# FlexSensor_and_Servo.net
KiCad netlist of a schematic drawn in EAGLE
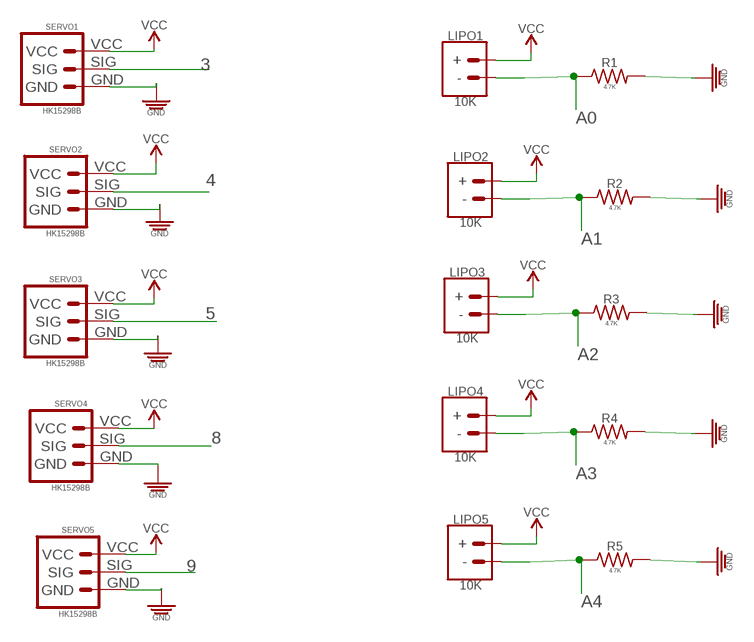
[diagram p0: schematic, sheet 1]

(export (version "E")
  (design (tool "Eeschema 10.0.6"))
  (components
    (comp (ref "LIPO1")
      (value "10K")
      (footprint "eagle-import:_MOLEX-89400_VERT_PITCH-2MM")
      (fields (field (name "MFR") "Spectra Symbol") (field (name "MPN") "FS-L-0095-103-ST"))
      (libsource (lib "eagle-import") (part "FLEX_SENSOR_89400_VERT-MALE_PITCH-2MM"))
    )
    (comp (ref "LIPO2")
      (value "10K")
      (footprint "eagle-import:_MOLEX-89400_VERT_PITCH-2MM")
      (fields (field (name "MFR") "Spectra Symbol") (field (name "MPN") "FS-L-0095-103-ST"))
      (libsource (lib "eagle-import") (part "FLEX_SENSOR_89400_VERT-MALE_PITCH-2MM"))
    )
    (comp (ref "LIPO3")
      (value "10K")
      (footprint "eagle-import:_MOLEX-89400_VERT_PITCH-2MM")
      (fields (field (name "MFR") "Spectra Symbol") (field (name "MPN") "FS-L-0095-103-ST"))
      (libsource (lib "eagle-import") (part "FLEX_SENSOR_89400_VERT-MALE_PITCH-2MM"))
    )
    (comp (ref "LIPO4")
      (value "10K")
      (footprint "eagle-import:_MOLEX-89400_VERT_PITCH-2MM")
      (fields (field (name "MFR") "Spectra Symbol") (field (name "MPN") "FS-L-0095-103-ST"))
      (libsource (lib "eagle-import") (part "FLEX_SENSOR_89400_VERT-MALE_PITCH-2MM"))
    )
    (comp (ref "LIPO5")
      (value "10K")
      (footprint "eagle-import:_MOLEX-89400_VERT_PITCH-2MM")
      (fields (field (name "MFR") "Spectra Symbol") (field (name "MPN") "FS-L-0095-103-ST"))
      (libsource (lib "eagle-import") (part "FLEX_SENSOR_89400_VERT-MALE_PITCH-2MM"))
    )
    (comp (ref "R1")
      (value "4.7K")
      (footprint "eagle-import:RESISTOR_SMD-805")
      (fields
        (field (name "MFR") "Yageo")
        (field (name "MPN") "RC0805JR-074K7L")
        (field (name "CREATOR") "MrSwirlyEyes")
      )
      (libsource (lib "eagle-import") (part "4.7KΩ_SMD-0805_1/8W-5%"))
    )
    (comp (ref "R2")
      (value "4.7K")
      (footprint "eagle-import:RESISTOR_SMD-805")
      (fields
        (field (name "MFR") "Yageo")
        (field (name "MPN") "RC0805JR-074K7L")
        (field (name "CREATOR") "MrSwirlyEyes")
      )
      (libsource (lib "eagle-import") (part "4.7KΩ_SMD-0805_1/8W-5%"))
    )
    (comp (ref "R3")
      (value "4.7K")
      (footprint "eagle-import:RESISTOR_SMD-805")
      (fields
        (field (name "MFR") "Yageo")
        (field (name "MPN") "RC0805JR-074K7L")
        (field (name "CREATOR") "MrSwirlyEyes")
      )
      (libsource (lib "eagle-import") (part "4.7KΩ_SMD-0805_1/8W-5%"))
    )
    (comp (ref "R4")
      (value "4.7K")
      (footprint "eagle-import:RESISTOR_SMD-805")
      (fields
        (field (name "MFR") "Yageo")
        (field (name "MPN") "RC0805JR-074K7L")
        (field (name "CREATOR") "MrSwirlyEyes")
      )
      (libsource (lib "eagle-import") (part "4.7KΩ_SMD-0805_1/8W-5%"))
    )
    (comp (ref "R5")
      (value "4.7K")
      (footprint "eagle-import:RESISTOR_SMD-805")
      (fields
        (field (name "MFR") "Yageo")
        (field (name "MPN") "RC0805JR-074K7L")
        (field (name "CREATOR") "MrSwirlyEyes")
      )
      (libsource (lib "eagle-import") (part "4.7KΩ_SMD-0805_1/8W-5%"))
    )
    (comp (ref "SERVO1")
      (value "HK15298B")
      (footprint "eagle-import:1X03-VERT-MALE")
      (fields (field (name "MFR") "HobbyKing"))
      (libsource (lib "eagle-import") (part "SERVO_SERVO-PN"))
    )
    (comp (ref "SERVO2")
      (value "HK15298B")
      (footprint "eagle-import:1X03-VERT-MALE")
      (fields (field (name "MFR") "HobbyKing"))
      (libsource (lib "eagle-import") (part "SERVO_SERVO-PN"))
    )
    (comp (ref "SERVO3")
      (value "HK15298B")
      (footprint "eagle-import:1X03-VERT-MALE")
      (fields (field (name "MFR") "HobbyKing"))
      (libsource (lib "eagle-import") (part "SERVO_SERVO-PN"))
    )
    (comp (ref "SERVO4")
      (value "HK15298B")
      (footprint "eagle-import:1X03-VERT-MALE")
      (fields (field (name "MFR") "HobbyKing"))
      (libsource (lib "eagle-import") (part "SERVO_SERVO-PN"))
    )
    (comp (ref "SERVO5")
      (value "HK15298B")
      (footprint "eagle-import:1X03-VERT-MALE")
      (fields (field (name "MFR") "HobbyKing"))
      (libsource (lib "eagle-import") (part "SERVO_SERVO-PN"))
    )
  )
  (nets
    (net (code "1") (name "/3") (class "Default")
      (node (ref "SERVO1") (pin "SIG") (pinfunction "SIG_SIG") (pintype "passive"))
    )
    (net (code "2") (name "/4") (class "Default")
      (node (ref "SERVO2") (pin "SIG") (pinfunction "SIG_SIG") (pintype "passive"))
    )
    (net (code "3") (name "/5") (class "Default")
      (node (ref "SERVO3") (pin "SIG") (pinfunction "SIG_SIG") (pintype "passive"))
    )
    (net (code "4") (name "/8") (class "Default")
      (node (ref "SERVO4") (pin "SIG") (pinfunction "SIG_SIG") (pintype "passive"))
    )
    (net (code "5") (name "/9") (class "Default")
      (node (ref "SERVO5") (pin "SIG") (pinfunction "SIG_SIG") (pintype "passive"))
    )
    (net (code "6") (name "/A0") (class "Default")
      (node (ref "LIPO1") (pin "2") (pinfunction "-_2") (pintype "passive"))
      (node (ref "R1") (pin "1") (pinfunction "1_1") (pintype "passive"))
    )
    (net (code "7") (name "/A1") (class "Default")
      (node (ref "LIPO2") (pin "2") (pinfunction "-_2") (pintype "passive"))
      (node (ref "R2") (pin "1") (pinfunction "1_1") (pintype "passive"))
    )
    (net (code "8") (name "/A2") (class "Default")
      (node (ref "LIPO3") (pin "2") (pinfunction "-_2") (pintype "passive"))
      (node (ref "R3") (pin "1") (pinfunction "1_1") (pintype "passive"))
    )
    (net (code "9") (name "/A3") (class "Default")
      (node (ref "LIPO4") (pin "2") (pinfunction "-_2") (pintype "passive"))
      (node (ref "R4") (pin "1") (pinfunction "1_1") (pintype "passive"))
    )
    (net (code "10") (name "/A4") (class "Default")
      (node (ref "LIPO5") (pin "2") (pinfunction "-_2") (pintype "passive"))
      (node (ref "R5") (pin "1") (pinfunction "1_1") (pintype "passive"))
    )
    (net (code "11") (name "GND") (class "Default")
      (node (ref "R1") (pin "2") (pinfunction "2_2") (pintype "passive"))
      (node (ref "R2") (pin "2") (pinfunction "2_2") (pintype "passive"))
      (node (ref "R3") (pin "2") (pinfunction "2_2") (pintype "passive"))
      (node (ref "R4") (pin "2") (pinfunction "2_2") (pintype "passive"))
      (node (ref "R5") (pin "2") (pinfunction "2_2") (pintype "passive"))
      (node (ref "SERVO1") (pin "GND") (pinfunction "GND_GND") (pintype "passive"))
      (node (ref "SERVO2") (pin "GND") (pinfunction "GND_GND") (pintype "passive"))
      (node (ref "SERVO3") (pin "GND") (pinfunction "GND_GND") (pintype "passive"))
      (node (ref "SERVO4") (pin "GND") (pinfunction "GND_GND") (pintype "passive"))
      (node (ref "SERVO5") (pin "GND") (pinfunction "GND_GND") (pintype "passive"))
    )
    (net (code "12") (name "VCC") (class "Default")
      (node (ref "LIPO1") (pin "1") (pinfunction "+_1") (pintype "passive"))
      (node (ref "LIPO2") (pin "1") (pinfunction "+_1") (pintype "passive"))
      (node (ref "LIPO3") (pin "1") (pinfunction "+_1") (pintype "passive"))
      (node (ref "LIPO4") (pin "1") (pinfunction "+_1") (pintype "passive"))
      (node (ref "LIPO5") (pin "1") (pinfunction "+_1") (pintype "passive"))
      (node (ref "SERVO1") (pin "VCC") (pinfunction "VCC_VCC") (pintype "passive"))
      (node (ref "SERVO2") (pin "VCC") (pinfunction "VCC_VCC") (pintype "passive"))
      (node (ref "SERVO3") (pin "VCC") (pinfunction "VCC_VCC") (pintype "passive"))
      (node (ref "SERVO4") (pin "VCC") (pinfunction "VCC_VCC") (pintype "passive"))
      (node (ref "SERVO5") (pin "VCC") (pinfunction "VCC_VCC") (pintype "passive"))
    )
  )
)
